# OneWireGateway_4x.net
KiCad netlist of a schematic drawn in EAGLE
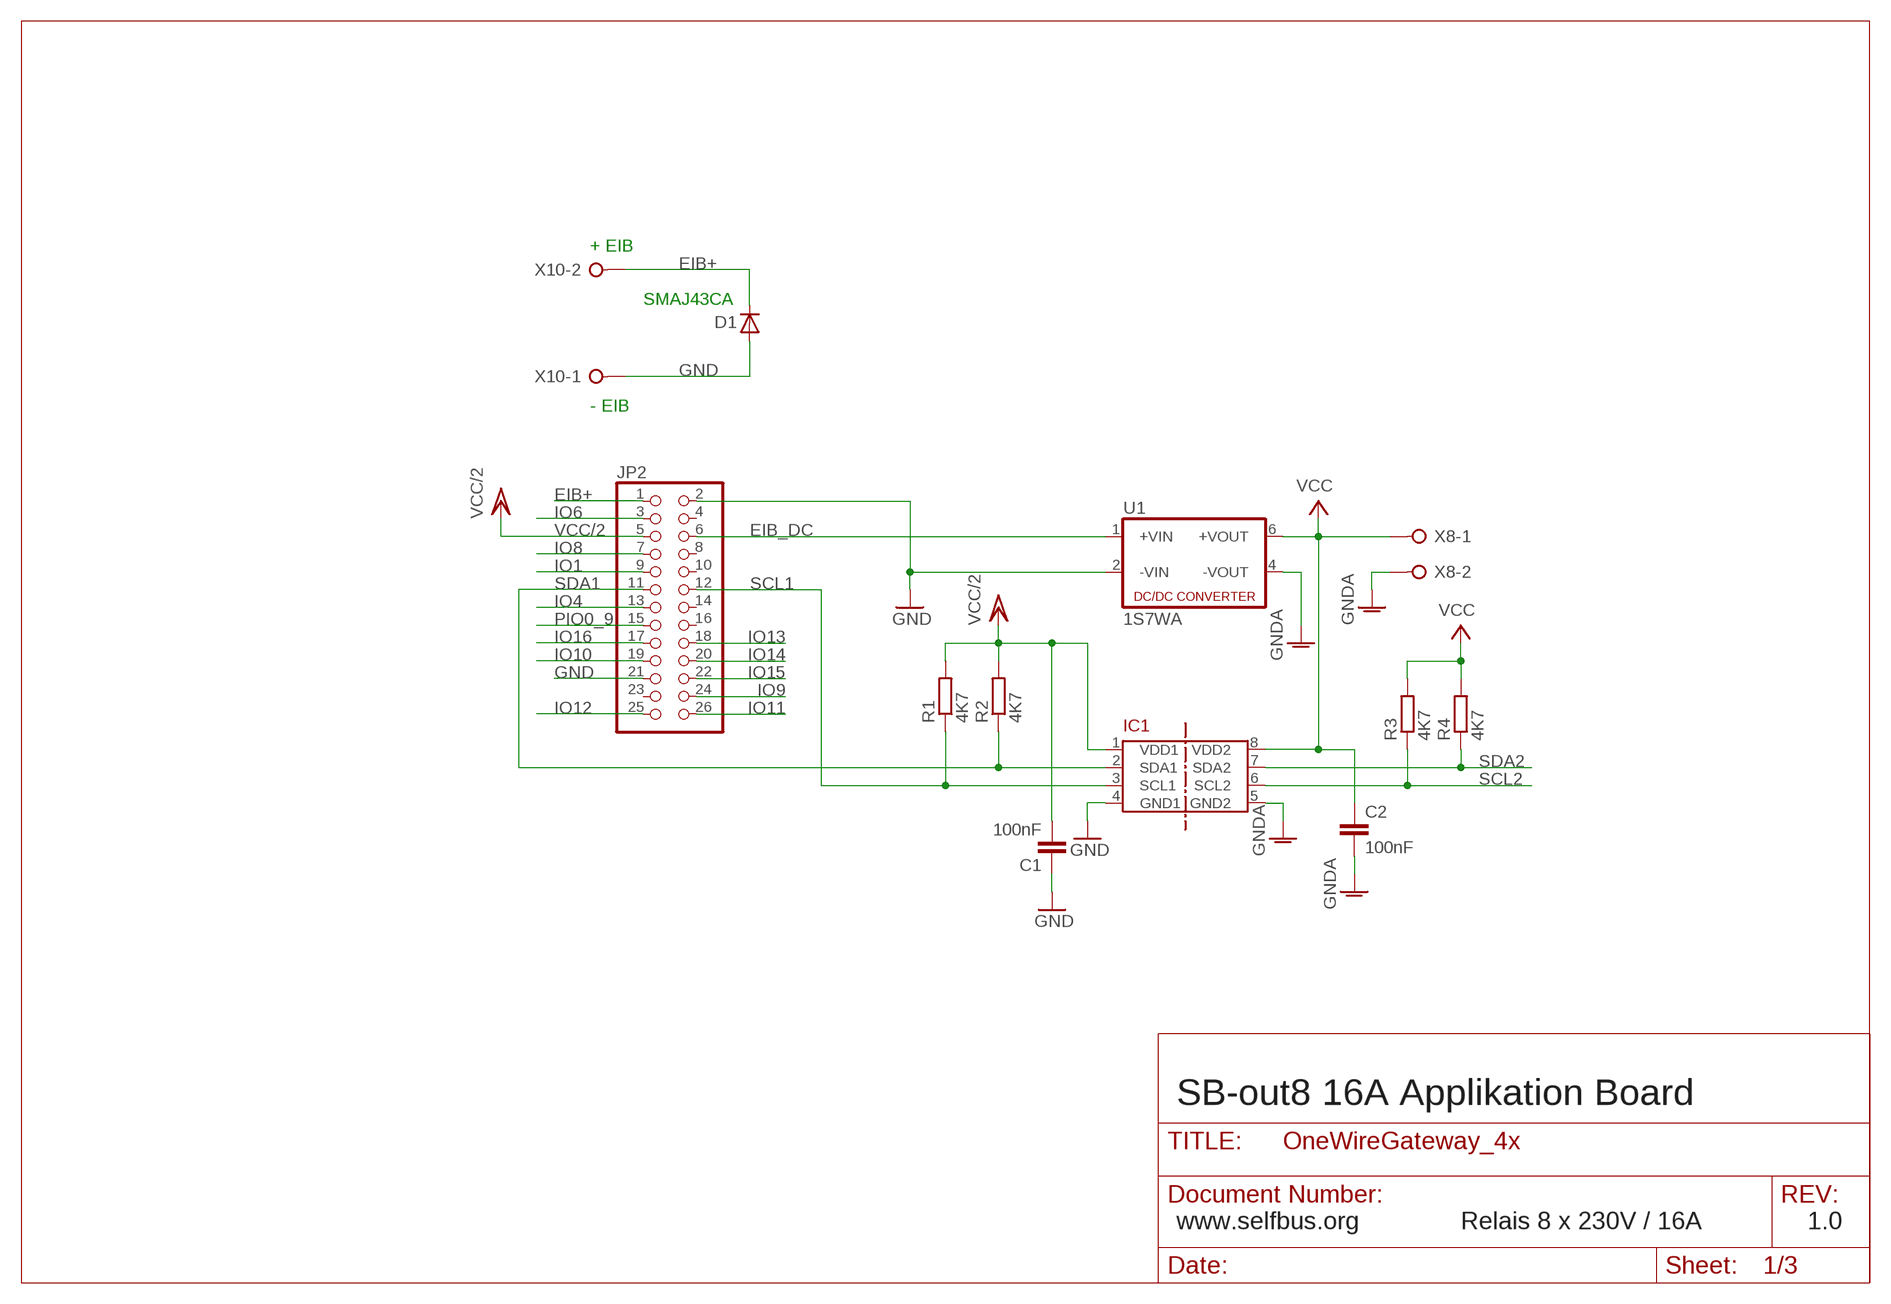
[diagram p0: schematic, sheet 1]
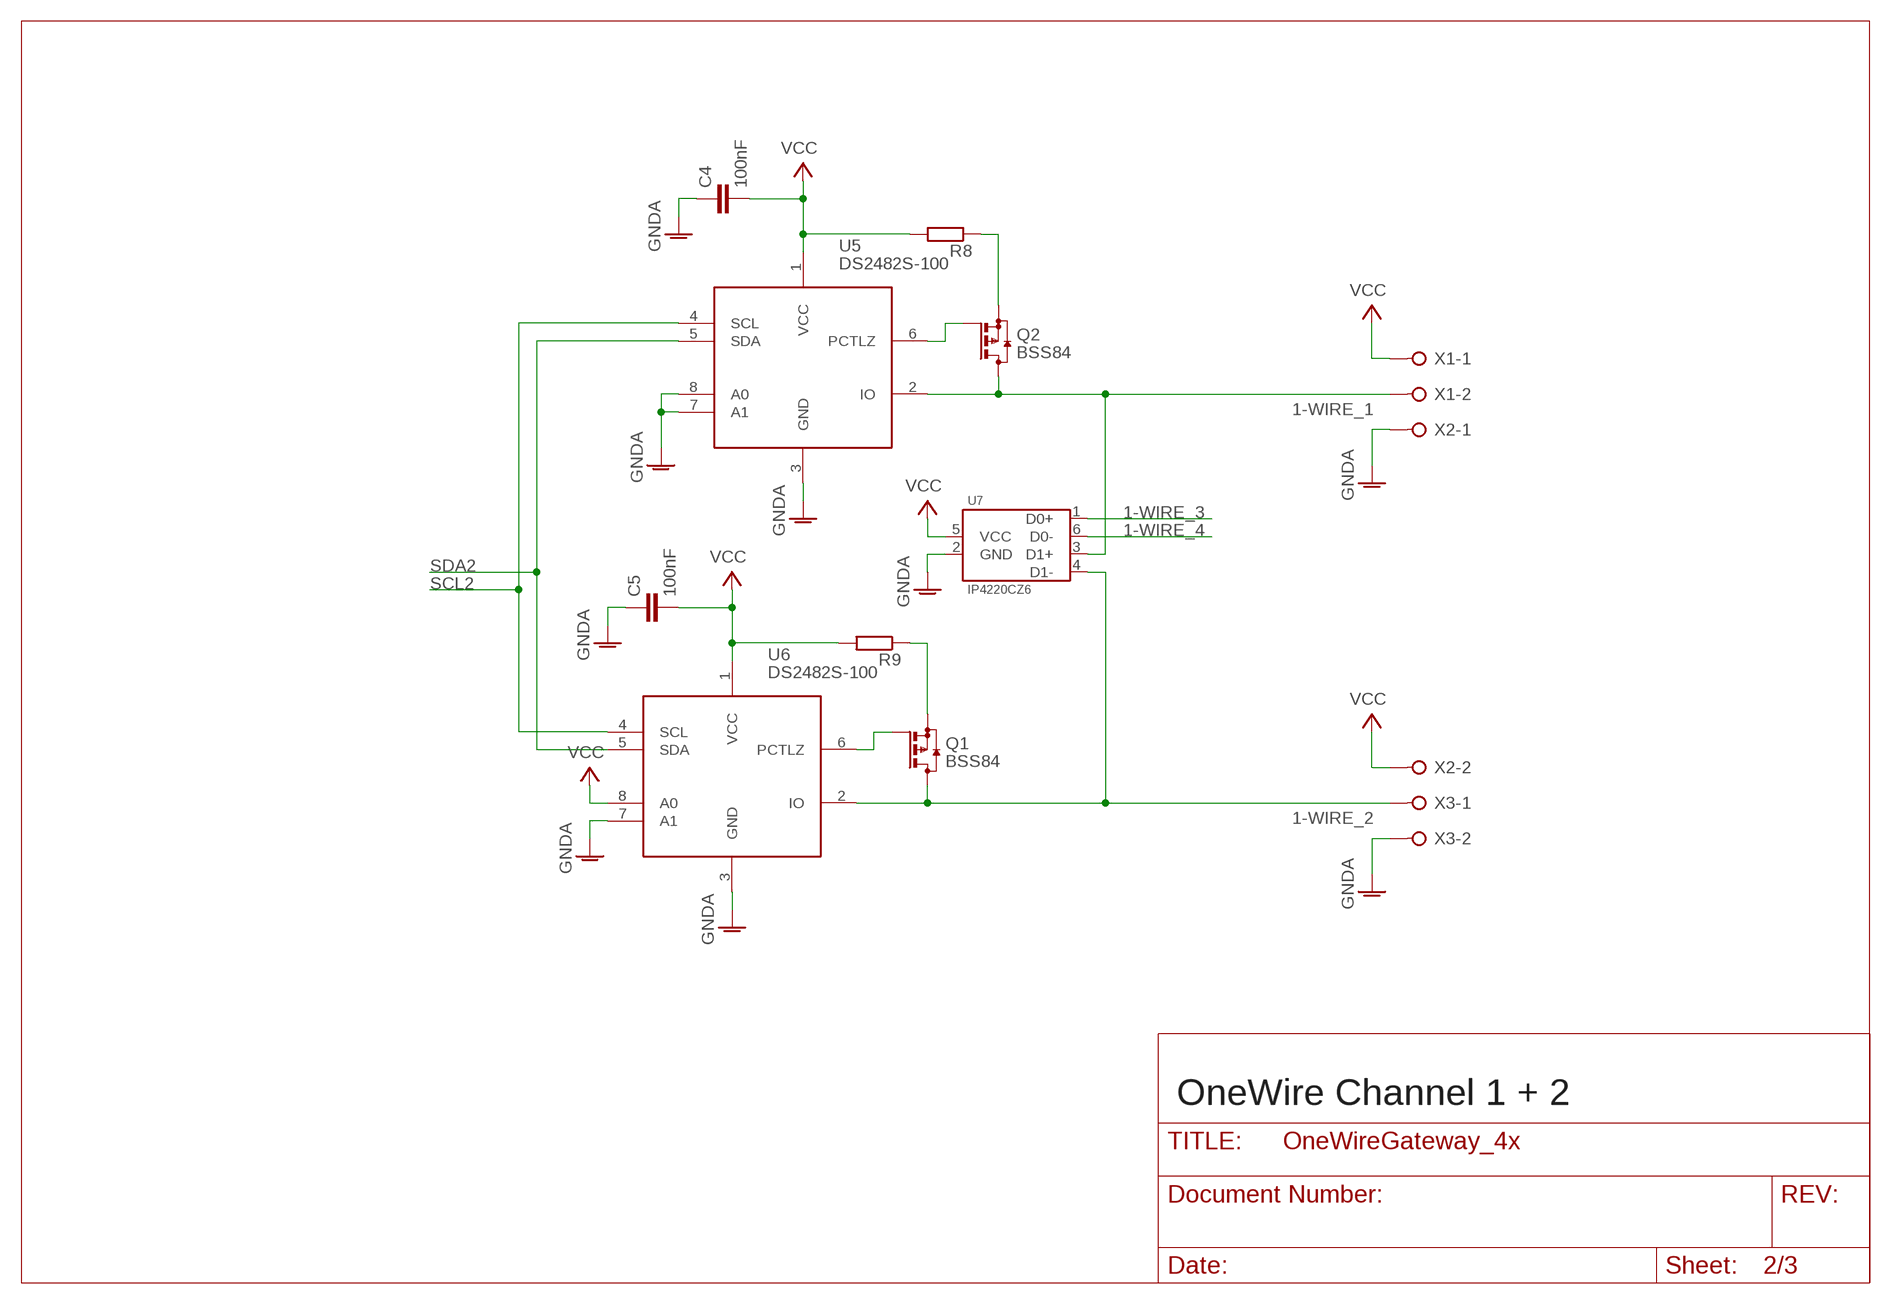
[diagram p1: schematic, sheet 2]
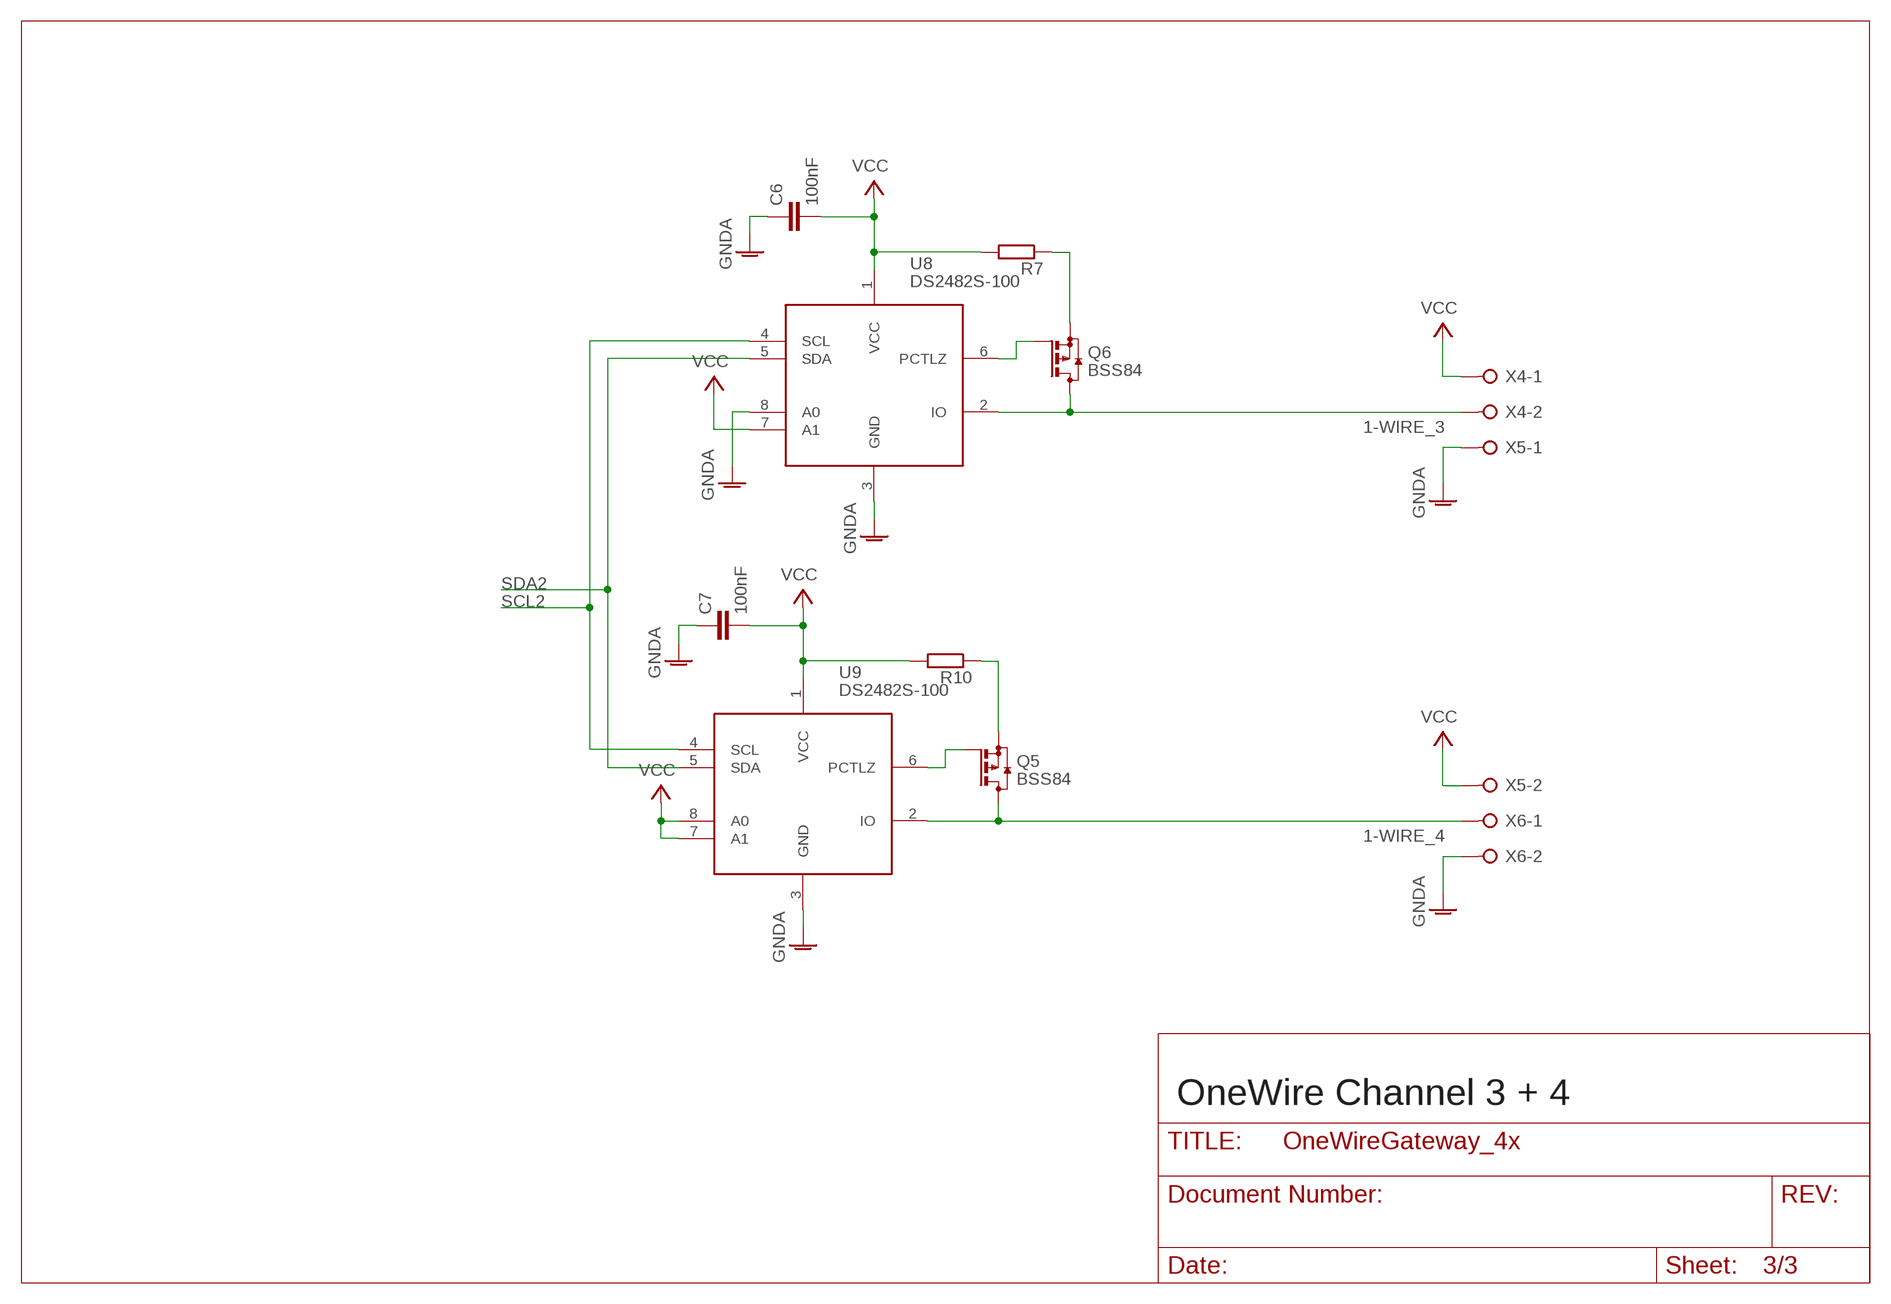
[diagram p2: schematic, sheet 3]

(export (version "E")
  (design (tool "Eeschema 10.0.6"))
  (components
    (comp (ref "C6")
      (value "100nF")
      (footprint "eagle-import:C0805")
      (libsource (lib "eagle-import") (part "C-EUC0805"))
    )
    (comp (ref "C7")
      (value "100nF")
      (footprint "eagle-import:C0805")
      (libsource (lib "eagle-import") (part "C-EUC0805"))
    )
    (comp (ref "Q5")
      (value "BSS84")
      (footprint "eagle-import:SOT23")
      (libsource (lib "eagle-import") (part "BSS84"))
    )
    (comp (ref "Q6")
      (value "BSS84")
      (footprint "eagle-import:SOT23")
      (libsource (lib "eagle-import") (part "BSS84"))
    )
    (comp (ref "R7")
      (value "R-EU_R0805")
      (footprint "eagle-import:R0805")
      (libsource (lib "eagle-import") (part "R-EU_R0805"))
    )
    (comp (ref "R10")
      (value "R-EU_R0805")
      (footprint "eagle-import:R0805")
      (libsource (lib "eagle-import") (part "R-EU_R0805"))
    )
    (comp (ref "U8")
      (value "DS2482S-100")
      (footprint "eagle-import:SO8")
      (fields (field (name "MF") "Maxim Integrated") (field (name "MPN") "DS2482-100+"))
      (libsource (lib "eagle-import") (part "DS2482-100+1"))
    )
    (comp (ref "U9")
      (value "DS2482S-100")
      (footprint "eagle-import:SO8")
      (fields (field (name "MF") "Maxim Integrated") (field (name "MPN") "DS2482-100+"))
      (libsource (lib "eagle-import") (part "DS2482-100+1"))
    )
    (comp (ref "X4")
      (value "W237-02P")
      (footprint "eagle-import:W237-132")
      (libsource (lib "eagle-import") (part "W237-02P"))
    )
    (comp (ref "X5")
      (value "W237-02P")
      (footprint "eagle-import:W237-132")
      (libsource (lib "eagle-import") (part "W237-02P"))
    )
    (comp (ref "X6")
      (value "W237-02P")
      (footprint "eagle-import:W237-132")
      (libsource (lib "eagle-import") (part "W237-02P"))
    )
    (comp (ref "C4")
      (value "100nF")
      (footprint "eagle-import:C0805")
      (libsource (lib "eagle-import") (part "C-EUC0805"))
    )
    (comp (ref "C5")
      (value "100nF")
      (footprint "eagle-import:C0805")
      (libsource (lib "eagle-import") (part "C-EUC0805"))
    )
    (comp (ref "Q1")
      (value "BSS84")
      (footprint "eagle-import:SOT23")
      (libsource (lib "eagle-import") (part "BSS84"))
    )
    (comp (ref "Q2")
      (value "BSS84")
      (footprint "eagle-import:SOT23")
      (libsource (lib "eagle-import") (part "BSS84"))
    )
    (comp (ref "R8")
      (value "R-EU_R0805")
      (footprint "eagle-import:R0805")
      (libsource (lib "eagle-import") (part "R-EU_R0805"))
    )
    (comp (ref "R9")
      (value "R-EU_R0805")
      (footprint "eagle-import:R0805")
      (libsource (lib "eagle-import") (part "R-EU_R0805"))
    )
    (comp (ref "U5")
      (value "DS2482S-100")
      (footprint "eagle-import:SO8")
      (fields (field (name "MF") "Maxim Integrated") (field (name "MPN") "DS2482-100+"))
      (libsource (lib "eagle-import") (part "DS2482-100+1"))
    )
    (comp (ref "U6")
      (value "DS2482S-100")
      (footprint "eagle-import:SO8")
      (fields (field (name "MF") "Maxim Integrated") (field (name "MPN") "DS2482-100+"))
      (libsource (lib "eagle-import") (part "DS2482-100+1"))
    )
    (comp (ref "U7")
      (value "IP4220CZ6")
      (footprint "eagle-import:SOT-6")
      (libsource (lib "eagle-import") (part "IP4220CZ6"))
    )
    (comp (ref "X1")
      (value "W237-02P")
      (footprint "eagle-import:W237-132")
      (libsource (lib "eagle-import") (part "W237-02P"))
    )
    (comp (ref "X2")
      (value "W237-02P")
      (footprint "eagle-import:W237-132")
      (libsource (lib "eagle-import") (part "W237-02P"))
    )
    (comp (ref "X3")
      (value "W237-02P")
      (footprint "eagle-import:W237-132")
      (libsource (lib "eagle-import") (part "W237-02P"))
    )
    (comp (ref "C1")
      (value "100nF")
      (footprint "eagle-import:C0805")
      (libsource (lib "eagle-import") (part "C-EUC0805"))
    )
    (comp (ref "C2")
      (value "100nF")
      (footprint "eagle-import:C0805")
      (libsource (lib "eagle-import") (part "C-EUC0805"))
    )
    (comp (ref "D1")
      (value "SMAJ40CA")
      (footprint "eagle-import:SMB")
      (libsource (lib "eagle-import") (part "D-SMB"))
    )
    (comp (ref "IC1")
      (value "ADUM1250")
      (footprint "eagle-import:SO08")
      (libsource (lib "eagle-import") (part "ADUM1250"))
    )
    (comp (ref "JP2")
      (value "PINHD-2X13_2.54-SMD")
      (footprint "eagle-import:2X13SMD")
      (libsource (lib "eagle-import") (part "PINHD-2X13_2.54-SMD"))
    )
    (comp (ref "R1")
      (value "4K7")
      (footprint "eagle-import:R0805")
      (libsource (lib "eagle-import") (part "R-EU_R0805"))
    )
    (comp (ref "R2")
      (value "4K7")
      (footprint "eagle-import:R0805")
      (libsource (lib "eagle-import") (part "R-EU_R0805"))
    )
    (comp (ref "R3")
      (value "4K7")
      (footprint "eagle-import:R0805")
      (libsource (lib "eagle-import") (part "R-EU_R0805"))
    )
    (comp (ref "R4")
      (value "4K7")
      (footprint "eagle-import:R0805")
      (libsource (lib "eagle-import") (part "R-EU_R0805"))
    )
    (comp (ref "U1")
      (value "1S7WA")
      (footprint "eagle-import:7PIN_SIP")
      (libsource (lib "eagle-import") (part "1S7WA"))
    )
    (comp (ref "X8")
      (value "W237-02P")
      (footprint "eagle-import:W237-132")
      (libsource (lib "eagle-import") (part "W237-02P"))
    )
    (comp (ref "X10")
      (value "W237-02P")
      (footprint "eagle-import:W237-132")
      (libsource (lib "eagle-import") (part "W237-02P"))
    )
  )
  (nets
    (net (code "1") (name "1-WIRE_1") (class "Default")
      (node (ref "Q2") (pin "3") (pinfunction "D_3") (pintype "passive"))
      (node (ref "U5") (pin "2") (pinfunction "IO_2") (pintype "bidirectional"))
      (node (ref "U7") (pin "3") (pinfunction "D1+_3") (pintype "bidirectional"))
      (node (ref "X1") (pin "2") (pinfunction "KL_2") (pintype "passive"))
    )
    (net (code "2") (name "1-WIRE_2") (class "Default")
      (node (ref "Q1") (pin "3") (pinfunction "D_3") (pintype "passive"))
      (node (ref "U6") (pin "2") (pinfunction "IO_2") (pintype "bidirectional"))
      (node (ref "U7") (pin "4") (pinfunction "D1-_4") (pintype "bidirectional"))
      (node (ref "X3") (pin "1") (pinfunction "KL_1") (pintype "passive"))
    )
    (net (code "3") (name "1-WIRE_3") (class "Default")
      (node (ref "Q6") (pin "3") (pinfunction "D_3") (pintype "passive"))
      (node (ref "U7") (pin "1") (pinfunction "D0+_1") (pintype "bidirectional"))
      (node (ref "U8") (pin "2") (pinfunction "IO_2") (pintype "bidirectional"))
      (node (ref "X4") (pin "2") (pinfunction "KL_2") (pintype "passive"))
    )
    (net (code "4") (name "1-WIRE_4") (class "Default")
      (node (ref "Q5") (pin "3") (pinfunction "D_3") (pintype "passive"))
      (node (ref "U7") (pin "6") (pinfunction "D0-_6") (pintype "bidirectional"))
      (node (ref "U9") (pin "2") (pinfunction "IO_2") (pintype "bidirectional"))
      (node (ref "X6") (pin "1") (pinfunction "KL_1") (pintype "passive"))
    )
    (net (code "5") (name "EIB+") (class "Default")
      (node (ref "D1") (pin "1") (pinfunction "C_1") (pintype "passive"))
      (node (ref "JP2") (pin "1") (pinfunction "1_1") (pintype "passive"))
      (node (ref "X10") (pin "2") (pinfunction "KL_2") (pintype "passive"))
    )
    (net (code "6") (name "EIB_DC") (class "Default")
      (node (ref "JP2") (pin "6") (pinfunction "6_6") (pintype "passive"))
      (node (ref "U1") (pin "1") (pinfunction "+VIN_1") (pintype "passive"))
    )
    (net (code "7") (name "GND") (class "Default")
      (node (ref "C1") (pin "1") (pinfunction "1_1") (pintype "passive"))
      (node (ref "D1") (pin "2") (pinfunction "A_2") (pintype "passive"))
      (node (ref "IC1") (pin "4") (pinfunction "GND1_4") (pintype "power_in"))
      (node (ref "JP2") (pin "2") (pinfunction "2_2") (pintype "passive"))
      (node (ref "JP2") (pin "21") (pinfunction "21_21") (pintype "passive"))
      (node (ref "U1") (pin "2") (pinfunction "-VIN_2") (pintype "passive"))
      (node (ref "X10") (pin "1") (pinfunction "KL_1") (pintype "passive"))
    )
    (net (code "8") (name "GNDA") (class "Default")
      (node (ref "C2") (pin "2") (pinfunction "2_2") (pintype "passive"))
      (node (ref "C4") (pin "1") (pinfunction "1_1") (pintype "passive"))
      (node (ref "C5") (pin "1") (pinfunction "1_1") (pintype "passive"))
      (node (ref "C6") (pin "1") (pinfunction "1_1") (pintype "passive"))
      (node (ref "C7") (pin "1") (pinfunction "1_1") (pintype "passive"))
      (node (ref "IC1") (pin "5") (pinfunction "GND2_5") (pintype "power_in"))
      (node (ref "U1") (pin "4") (pinfunction "-VOUT_4") (pintype "passive"))
      (node (ref "U5") (pin "3") (pinfunction "GND_3") (pintype "bidirectional"))
      (node (ref "U5") (pin "7") (pinfunction "A1_7") (pintype "bidirectional"))
      (node (ref "U5") (pin "8") (pinfunction "A0_8") (pintype "bidirectional"))
      (node (ref "U6") (pin "3") (pinfunction "GND_3") (pintype "bidirectional"))
      (node (ref "U6") (pin "7") (pinfunction "A1_7") (pintype "bidirectional"))
      (node (ref "U7") (pin "2") (pinfunction "GND_2") (pintype "bidirectional"))
      (node (ref "U8") (pin "3") (pinfunction "GND_3") (pintype "bidirectional"))
      (node (ref "U8") (pin "8") (pinfunction "A0_8") (pintype "bidirectional"))
      (node (ref "U9") (pin "3") (pinfunction "GND_3") (pintype "bidirectional"))
      (node (ref "X2") (pin "1") (pinfunction "KL_1") (pintype "passive"))
      (node (ref "X3") (pin "2") (pinfunction "KL_2") (pintype "passive"))
      (node (ref "X5") (pin "1") (pinfunction "KL_1") (pintype "passive"))
      (node (ref "X6") (pin "2") (pinfunction "KL_2") (pintype "passive"))
      (node (ref "X8") (pin "2") (pinfunction "KL_2") (pintype "passive"))
    )
    (net (code "9") (name "IO1") (class "Default")
      (node (ref "JP2") (pin "9") (pinfunction "9_9") (pintype "passive"))
    )
    (net (code "10") (name "IO4") (class "Default")
      (node (ref "JP2") (pin "13") (pinfunction "13_13") (pintype "passive"))
    )
    (net (code "11") (name "IO6") (class "Default")
      (node (ref "JP2") (pin "3") (pinfunction "3_3") (pintype "passive"))
    )
    (net (code "12") (name "IO8") (class "Default")
      (node (ref "JP2") (pin "7") (pinfunction "7_7") (pintype "passive"))
    )
    (net (code "13") (name "IO9") (class "Default")
      (node (ref "JP2") (pin "24") (pinfunction "24_24") (pintype "passive"))
    )
    (net (code "14") (name "IO10") (class "Default")
      (node (ref "JP2") (pin "19") (pinfunction "19_19") (pintype "passive"))
    )
    (net (code "15") (name "IO11") (class "Default")
      (node (ref "JP2") (pin "26") (pinfunction "26_26") (pintype "passive"))
    )
    (net (code "16") (name "IO12") (class "Default")
      (node (ref "JP2") (pin "25") (pinfunction "25_25") (pintype "passive"))
    )
    (net (code "17") (name "IO13") (class "Default")
      (node (ref "JP2") (pin "18") (pinfunction "18_18") (pintype "passive"))
    )
    (net (code "18") (name "IO14") (class "Default")
      (node (ref "JP2") (pin "20") (pinfunction "20_20") (pintype "passive"))
    )
    (net (code "19") (name "IO15") (class "Default")
      (node (ref "JP2") (pin "22") (pinfunction "22_22") (pintype "passive"))
    )
    (net (code "20") (name "IO16") (class "Default")
      (node (ref "JP2") (pin "17") (pinfunction "17_17") (pintype "passive"))
    )
    (net (code "21") (name "Net-(Q1-G)") (class "Default")
      (node (ref "Q1") (pin "1") (pinfunction "G_1") (pintype "passive"))
      (node (ref "U6") (pin "6") (pinfunction "PCTLZ_6") (pintype "bidirectional"))
    )
    (net (code "22") (name "Net-(Q1-S)") (class "Default")
      (node (ref "Q1") (pin "2") (pinfunction "S_2") (pintype "passive"))
      (node (ref "R9") (pin "1") (pinfunction "1_1") (pintype "passive"))
    )
    (net (code "23") (name "Net-(Q2-G)") (class "Default")
      (node (ref "Q2") (pin "1") (pinfunction "G_1") (pintype "passive"))
      (node (ref "U5") (pin "6") (pinfunction "PCTLZ_6") (pintype "bidirectional"))
    )
    (net (code "24") (name "Net-(Q2-S)") (class "Default")
      (node (ref "Q2") (pin "2") (pinfunction "S_2") (pintype "passive"))
      (node (ref "R8") (pin "1") (pinfunction "1_1") (pintype "passive"))
    )
    (net (code "25") (name "Net-(Q5-G)") (class "Default")
      (node (ref "Q5") (pin "1") (pinfunction "G_1") (pintype "passive"))
      (node (ref "U9") (pin "6") (pinfunction "PCTLZ_6") (pintype "bidirectional"))
    )
    (net (code "26") (name "Net-(Q5-S)") (class "Default")
      (node (ref "Q5") (pin "2") (pinfunction "S_2") (pintype "passive"))
      (node (ref "R10") (pin "1") (pinfunction "1_1") (pintype "passive"))
    )
    (net (code "27") (name "Net-(Q6-G)") (class "Default")
      (node (ref "Q6") (pin "1") (pinfunction "G_1") (pintype "passive"))
      (node (ref "U8") (pin "6") (pinfunction "PCTLZ_6") (pintype "bidirectional"))
    )
    (net (code "28") (name "Net-(Q6-S)") (class "Default")
      (node (ref "Q6") (pin "2") (pinfunction "S_2") (pintype "passive"))
      (node (ref "R7") (pin "1") (pinfunction "1_1") (pintype "passive"))
    )
    (net (code "29") (name "PIO0_9") (class "Default")
      (node (ref "JP2") (pin "15") (pinfunction "15_15") (pintype "passive"))
    )
    (net (code "30") (name "SCL1") (class "Default")
      (node (ref "IC1") (pin "3") (pinfunction "SCL1_3") (pintype "bidirectional"))
      (node (ref "JP2") (pin "12") (pinfunction "12_12") (pintype "passive"))
      (node (ref "R1") (pin "1") (pinfunction "1_1") (pintype "passive"))
    )
    (net (code "31") (name "SCL2") (class "Default")
      (node (ref "IC1") (pin "6") (pinfunction "SCL2_6") (pintype "bidirectional"))
      (node (ref "R3") (pin "1") (pinfunction "1_1") (pintype "passive"))
      (node (ref "U5") (pin "4") (pinfunction "SCL_4") (pintype "bidirectional"))
      (node (ref "U6") (pin "4") (pinfunction "SCL_4") (pintype "bidirectional"))
      (node (ref "U8") (pin "4") (pinfunction "SCL_4") (pintype "bidirectional"))
      (node (ref "U9") (pin "4") (pinfunction "SCL_4") (pintype "bidirectional"))
    )
    (net (code "32") (name "SDA1") (class "Default")
      (node (ref "IC1") (pin "2") (pinfunction "SDA1_2") (pintype "bidirectional"))
      (node (ref "JP2") (pin "11") (pinfunction "11_11") (pintype "passive"))
      (node (ref "R2") (pin "1") (pinfunction "1_1") (pintype "passive"))
    )
    (net (code "33") (name "SDA2") (class "Default")
      (node (ref "IC1") (pin "7") (pinfunction "SDA2_7") (pintype "bidirectional"))
      (node (ref "R4") (pin "1") (pinfunction "1_1") (pintype "passive"))
      (node (ref "U5") (pin "5") (pinfunction "SDA_5") (pintype "bidirectional"))
      (node (ref "U6") (pin "5") (pinfunction "SDA_5") (pintype "bidirectional"))
      (node (ref "U8") (pin "5") (pinfunction "SDA_5") (pintype "bidirectional"))
      (node (ref "U9") (pin "5") (pinfunction "SDA_5") (pintype "bidirectional"))
    )
    (net (code "34") (name "VCC") (class "Default")
      (node (ref "C2") (pin "1") (pinfunction "1_1") (pintype "passive"))
      (node (ref "C4") (pin "2") (pinfunction "2_2") (pintype "passive"))
      (node (ref "C5") (pin "2") (pinfunction "2_2") (pintype "passive"))
      (node (ref "C6") (pin "2") (pinfunction "2_2") (pintype "passive"))
      (node (ref "C7") (pin "2") (pinfunction "2_2") (pintype "passive"))
      (node (ref "IC1") (pin "8") (pinfunction "VDD2_8") (pintype "power_in"))
      (node (ref "R10") (pin "2") (pinfunction "2_2") (pintype "passive"))
      (node (ref "R3") (pin "2") (pinfunction "2_2") (pintype "passive"))
      (node (ref "R4") (pin "2") (pinfunction "2_2") (pintype "passive"))
      (node (ref "R7") (pin "2") (pinfunction "2_2") (pintype "passive"))
      (node (ref "R8") (pin "2") (pinfunction "2_2") (pintype "passive"))
      (node (ref "R9") (pin "2") (pinfunction "2_2") (pintype "passive"))
      (node (ref "U1") (pin "6") (pinfunction "+VOUT_6") (pintype "passive"))
      (node (ref "U5") (pin "1") (pinfunction "VCC_1") (pintype "bidirectional"))
      (node (ref "U6") (pin "1") (pinfunction "VCC_1") (pintype "bidirectional"))
      (node (ref "U6") (pin "8") (pinfunction "A0_8") (pintype "bidirectional"))
      (node (ref "U7") (pin "5") (pinfunction "VCC_5") (pintype "bidirectional"))
      (node (ref "U8") (pin "1") (pinfunction "VCC_1") (pintype "bidirectional"))
      (node (ref "U8") (pin "7") (pinfunction "A1_7") (pintype "bidirectional"))
      (node (ref "U9") (pin "1") (pinfunction "VCC_1") (pintype "bidirectional"))
      (node (ref "U9") (pin "7") (pinfunction "A1_7") (pintype "bidirectional"))
      (node (ref "U9") (pin "8") (pinfunction "A0_8") (pintype "bidirectional"))
      (node (ref "X1") (pin "1") (pinfunction "KL_1") (pintype "passive"))
      (node (ref "X2") (pin "2") (pinfunction "KL_2") (pintype "passive"))
      (node (ref "X4") (pin "1") (pinfunction "KL_1") (pintype "passive"))
      (node (ref "X5") (pin "2") (pinfunction "KL_2") (pintype "passive"))
      (node (ref "X8") (pin "1") (pinfunction "KL_1") (pintype "passive"))
    )
    (net (code "35") (name "VCC{slash}2") (class "Default")
      (node (ref "C1") (pin "2") (pinfunction "2_2") (pintype "passive"))
      (node (ref "IC1") (pin "1") (pinfunction "VDD1_1") (pintype "power_in"))
      (node (ref "JP2") (pin "5") (pinfunction "5_5") (pintype "passive"))
      (node (ref "R1") (pin "2") (pinfunction "2_2") (pintype "passive"))
      (node (ref "R2") (pin "2") (pinfunction "2_2") (pintype "passive"))
    )
    (net (code "36") (name "unconnected-(JP2-Pad4)") (class "Default")
      (node (ref "JP2") (pin "4") (pinfunction "4_4") (pintype "passive"))
    )
    (net (code "37") (name "unconnected-(JP2-Pad8)") (class "Default")
      (node (ref "JP2") (pin "8") (pinfunction "8_8") (pintype "passive"))
    )
    (net (code "38") (name "unconnected-(JP2-Pad10)") (class "Default")
      (node (ref "JP2") (pin "10") (pinfunction "10_10") (pintype "passive"))
    )
    (net (code "39") (name "unconnected-(JP2-Pad14)") (class "Default")
      (node (ref "JP2") (pin "14") (pinfunction "14_14") (pintype "passive"))
    )
    (net (code "40") (name "unconnected-(JP2-Pad16)") (class "Default")
      (node (ref "JP2") (pin "16") (pinfunction "16_16") (pintype "passive"))
    )
    (net (code "41") (name "unconnected-(JP2-Pad23)") (class "Default")
      (node (ref "JP2") (pin "23") (pinfunction "23_23") (pintype "passive"))
    )
  )
)
